# ulchich-variant.net
KiCad netlist of a schematic drawn in Altium Designer
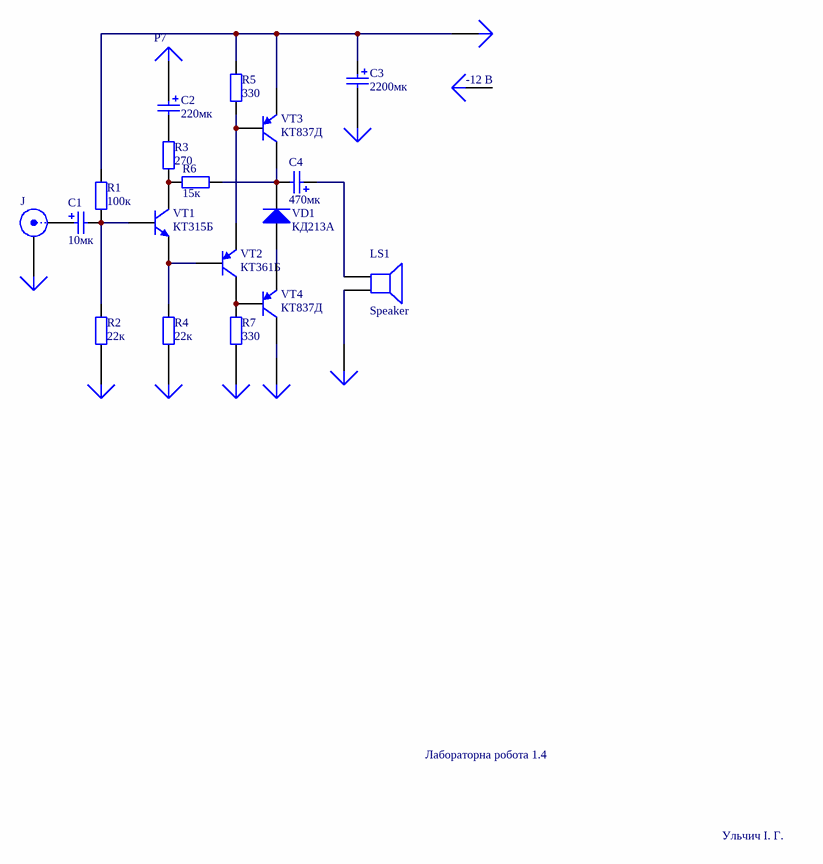
[diagram p0: ulchich-variant.SchDoc]

(export (version "E")
  (design (tool "Eeschema 10.0.6"))
  (components
    (comp (ref "C1")
      (value "10мк")
      (footprint "CAPPA14.05-10.5x6.3")
      (description "Polarized Capacitor (Axial)")
      (fields (field (name "Comment") "Cap Pol2") (field (name "PUBLISHER") "Altium Limited"))
      (libsource (lib "Miscellaneous Devices") (part "Cap Pol2"))
    )
    (comp (ref "C2")
      (value "220мк")
      (footprint "CAPPA14.05-10.5x6.3")
      (description "Polarized Capacitor (Axial)")
      (fields (field (name "Comment") "Cap Pol2") (field (name "PUBLISHER") "Altium Limited"))
      (libsource (lib "Miscellaneous Devices") (part "Cap Pol2"))
    )
    (comp (ref "C3")
      (value "2200мк")
      (footprint "CAPPA14.05-10.5x6.3")
      (description "Polarized Capacitor (Axial)")
      (fields (field (name "Comment") "Cap Pol2") (field (name "PUBLISHER") "Altium Limited"))
      (libsource (lib "Miscellaneous Devices") (part "Cap Pol2"))
    )
    (comp (ref "C4")
      (value "470мк")
      (footprint "CAPPA14.05-10.5x6.3")
      (description "Polarized Capacitor (Axial)")
      (fields (field (name "Comment") "Cap Pol2") (field (name "PUBLISHER") "Altium Limited"))
      (libsource (lib "Miscellaneous Devices") (part "Cap Pol2"))
    )
    (comp (ref "J")
      (value "BNC")
      (footprint "BNC_RA CON")
      (description "BNC Elbow Connector")
      (fields (field (name "PUBLISHER") "Altium Limited"))
      (libsource (lib "Miscellaneous Connectors") (part "BNC"))
    )
    (comp (ref "LS1")
      (value "Speaker")
      (footprint "PIN2")
      (description "Loudspeaker")
      (fields (field (name "PUBLISHER") "Altium Limited"))
      (libsource (lib "Miscellaneous Devices") (part "Speaker"))
    )
    (comp (ref "P1")
      (value "Plug")
      (footprint "PIN1")
      (fields (field (name "PUBLISHER") "Altium Limited"))
      (libsource (lib "Miscellaneous Connectors") (part "Plug"))
    )
    (comp (ref "P2")
      (value "Plug")
      (footprint "PIN1")
      (fields (field (name "PUBLISHER") "Altium Limited"))
      (libsource (lib "Miscellaneous Connectors") (part "Plug"))
    )
    (comp (ref "P3")
      (value "Plug")
      (footprint "PIN1")
      (fields (field (name "PUBLISHER") "Altium Limited"))
      (libsource (lib "Miscellaneous Connectors") (part "Plug"))
    )
    (comp (ref "P4")
      (value "Plug")
      (footprint "PIN1")
      (fields (field (name "PUBLISHER") "Altium Limited"))
      (libsource (lib "Miscellaneous Connectors") (part "Plug"))
    )
    (comp (ref "P5")
      (value "Plug")
      (footprint "PIN1")
      (fields (field (name "PUBLISHER") "Altium Limited"))
      (libsource (lib "Miscellaneous Connectors") (part "Plug"))
    )
    (comp (ref "P6")
      (value "Plug")
      (footprint "PIN1")
      (fields (field (name "PUBLISHER") "Altium Limited"))
      (libsource (lib "Miscellaneous Connectors") (part "Plug"))
    )
    (comp (ref "P7")
      (value "Plug")
      (footprint "PIN1")
      (fields (field (name "PUBLISHER") "Altium Limited"))
      (libsource (lib "Miscellaneous Connectors") (part "Plug"))
    )
    (comp (ref "P8")
      (value "Plug")
      (footprint "PIN1")
      (fields (field (name "PUBLISHER") "Altium Limited"))
      (libsource (lib "Miscellaneous Connectors") (part "Plug"))
    )
    (comp (ref "P9")
      (value "Plug")
      (footprint "PIN1")
      (fields (field (name "PUBLISHER") "Altium Limited"))
      (libsource (lib "Miscellaneous Connectors") (part "Plug"))
    )
    (comp (ref "P10")
      (value "-12 В")
      (footprint "PIN1")
      (description "Plug")
      (fields (field (name "PUBLISHER") "Altium Limited"))
      (libsource (lib "Miscellaneous Connectors") (part "Plug"))
    )
    (comp (ref "R1")
      (value "100к")
      (footprint "AXIAL-0.4")
      (description "Resistor")
      (fields (field (name "Comment") "Res2") (field (name "PUBLISHER") "Altium Limited"))
      (libsource (lib "Miscellaneous Devices") (part "Res2"))
    )
    (comp (ref "R2")
      (value "22к")
      (footprint "AXIAL-0.4")
      (description "Resistor")
      (fields (field (name "Comment") "Res2") (field (name "PUBLISHER") "Altium Limited"))
      (libsource (lib "Miscellaneous Devices") (part "Res2"))
    )
    (comp (ref "R3")
      (value "270")
      (footprint "AXIAL-0.4")
      (description "Resistor")
      (fields (field (name "Comment") "Res2") (field (name "PUBLISHER") "Altium Limited"))
      (libsource (lib "Miscellaneous Devices") (part "Res2"))
    )
    (comp (ref "R4")
      (value "22к")
      (footprint "AXIAL-0.4")
      (description "Resistor")
      (fields (field (name "Comment") "Res2") (field (name "PUBLISHER") "Altium Limited"))
      (libsource (lib "Miscellaneous Devices") (part "Res2"))
    )
    (comp (ref "R5")
      (value "330")
      (footprint "AXIAL-0.4")
      (description "Resistor")
      (fields (field (name "Comment") "Res2") (field (name "PUBLISHER") "Altium Limited"))
      (libsource (lib "Miscellaneous Devices") (part "Res2"))
    )
    (comp (ref "R6")
      (value "15к")
      (footprint "AXIAL-0.4")
      (description "Resistor")
      (fields (field (name "Comment") "Res2") (field (name "PUBLISHER") "Altium Limited"))
      (libsource (lib "") (part "Res2_1"))
    )
    (comp (ref "R7")
      (value "330")
      (footprint "AXIAL-0.4")
      (description "Resistor")
      (fields (field (name "Comment") "Res2") (field (name "PUBLISHER") "Altium Limited"))
      (libsource (lib "Miscellaneous Devices") (part "Res2"))
    )
    (comp (ref "VD1")
      (value "КД213А")
      (footprint "SMC")
      (description "Default Diode")
      (fields (field (name "PUBLISHER") "Altium Limited"))
      (libsource (lib "Miscellaneous Devices") (part "Diode"))
    )
    (comp (ref "VT1")
      (value "КТ315Б")
      (footprint "TO-226")
      (description "NPN Bipolar Transistor")
      (fields (field (name "PUBLISHER") "Altium Limited"))
      (libsource (lib "Miscellaneous Devices") (part "NPN"))
    )
    (comp (ref "VT2")
      (value "КТ361Б")
      (footprint "SOT-23B")
      (description "PNP Bipolar Transistor")
      (fields (field (name "PUBLISHER") "Altium Limited"))
      (libsource (lib "Miscellaneous Devices") (part "PNP"))
    )
    (comp (ref "VT3")
      (value "КТ837Д")
      (footprint "SOT-23B")
      (description "PNP Bipolar Transistor")
      (fields (field (name "PUBLISHER") "Altium Limited"))
      (libsource (lib "Miscellaneous Devices") (part "PNP"))
    )
    (comp (ref "VT4")
      (value "КТ837Д")
      (footprint "SOT-23B")
      (description "PNP Bipolar Transistor")
      (fields (field (name "PUBLISHER") "Altium Limited"))
      (libsource (lib "Miscellaneous Devices") (part "PNP"))
    )
  )
  (nets
    (net (code "1") (name "Net-(C2-Pad1)") (class "Default")
      (node (ref "C2") (pin "1") (pinfunction "1_1") (pintype "passive"))
      (node (ref "P7") (pin "1") (pinfunction "1_1") (pintype "passive"))
    )
    (net (code "2") (name "Net-(C2-Pad2)") (class "Default")
      (node (ref "C2") (pin "2") (pinfunction "2_2") (pintype "passive"))
      (node (ref "R3") (pin "2") (pinfunction "2_2") (pintype "passive"))
    )
    (net (code "3") (name "Net-(C3-Pad2)") (class "Default")
      (node (ref "C3") (pin "2") (pinfunction "2_2") (pintype "passive"))
      (node (ref "P1") (pin "1") (pinfunction "1_1") (pintype "passive"))
    )
    (net (code "4") (name "Net-(C4-Pad1)") (class "Default")
      (node (ref "C4") (pin "1") (pinfunction "1_1") (pintype "passive"))
      (node (ref "LS1") (pin "1") (pinfunction "1_1") (pintype "passive"))
    )
    (net (code "5") (name "Net-(J-X)") (class "Default")
      (node (ref "C1") (pin "1") (pinfunction "1_1") (pintype "passive"))
      (node (ref "J") (pin "1") (pinfunction "X_1") (pintype "passive"))
    )
    (net (code "6") (name "Net-(J-Y)") (class "Default")
      (node (ref "J") (pin "2") (pinfunction "Y_2") (pintype "passive"))
      (node (ref "P9") (pin "1") (pinfunction "1_1") (pintype "passive"))
    )
    (net (code "7") (name "Net-(LS1-Pad2)") (class "Default")
      (node (ref "LS1") (pin "2") (pinfunction "2_2") (pintype "passive"))
      (node (ref "P2") (pin "1") (pinfunction "1_1") (pintype "passive"))
    )
    (net (code "8") (name "Net-(P3-Pad1)") (class "Default")
      (node (ref "P3") (pin "1") (pinfunction "1_1") (pintype "passive"))
      (node (ref "R7") (pin "1") (pinfunction "1_1") (pintype "passive"))
    )
    (net (code "9") (name "Net-(P4-Pad1)") (class "Default")
      (node (ref "P4") (pin "1") (pinfunction "1_1") (pintype "passive"))
      (node (ref "R4") (pin "1") (pinfunction "1_1") (pintype "passive"))
    )
    (net (code "10") (name "Net-(P5-Pad1)") (class "Default")
      (node (ref "P5") (pin "1") (pinfunction "1_1") (pintype "passive"))
      (node (ref "R2") (pin "1") (pinfunction "1_1") (pintype "passive"))
    )
    (net (code "11") (name "Net-(VD1-A)") (class "Default")
      (node (ref "VD1") (pin "1") (pinfunction "A_1") (pintype "passive"))
      (node (ref "VT4") (pin "3") (pinfunction "E_3") (pintype "passive"))
    )
    (net (code "12") (name "Net-(VD1-K)") (class "Default")
      (node (ref "C4") (pin "2") (pinfunction "2_2") (pintype "passive"))
      (node (ref "R6") (pin "2") (pinfunction "2_2") (pintype "passive"))
      (node (ref "VD1") (pin "2") (pinfunction "K_2") (pintype "passive"))
      (node (ref "VT3") (pin "1") (pinfunction "C_1") (pintype "passive"))
    )
    (net (code "13") (name "Net-(VT1-B)") (class "Default")
      (node (ref "C1") (pin "2") (pinfunction "2_2") (pintype "passive"))
      (node (ref "R1") (pin "1") (pinfunction "1_1") (pintype "passive"))
      (node (ref "R2") (pin "2") (pinfunction "2_2") (pintype "passive"))
      (node (ref "VT1") (pin "2") (pinfunction "B_2") (pintype "passive"))
    )
    (net (code "14") (name "Net-(VT1-C)") (class "Default")
      (node (ref "R3") (pin "1") (pinfunction "1_1") (pintype "passive"))
      (node (ref "R6") (pin "1") (pinfunction "1_1") (pintype "passive"))
      (node (ref "VT1") (pin "1") (pinfunction "C_1") (pintype "passive"))
    )
    (net (code "15") (name "Net-(VT1-E)") (class "Default")
      (node (ref "R4") (pin "2") (pinfunction "2_2") (pintype "passive"))
      (node (ref "VT1") (pin "3") (pinfunction "E_3") (pintype "passive"))
      (node (ref "VT2") (pin "2") (pinfunction "B_2") (pintype "passive"))
    )
    (net (code "16") (name "Net-(VT2-C)") (class "Default")
      (node (ref "R7") (pin "2") (pinfunction "2_2") (pintype "passive"))
      (node (ref "VT2") (pin "1") (pinfunction "C_1") (pintype "passive"))
      (node (ref "VT4") (pin "2") (pinfunction "B_2") (pintype "passive"))
    )
    (net (code "17") (name "Net-(VT2-E)") (class "Default")
      (node (ref "R5") (pin "1") (pinfunction "1_1") (pintype "passive"))
      (node (ref "VT2") (pin "3") (pinfunction "E_3") (pintype "passive"))
      (node (ref "VT3") (pin "2") (pinfunction "B_2") (pintype "passive"))
    )
    (net (code "18") (name "Net-(VT3-E)") (class "Default")
      (node (ref "C3") (pin "1") (pinfunction "1_1") (pintype "passive"))
      (node (ref "P6") (pin "1") (pinfunction "1_1") (pintype "passive"))
      (node (ref "R1") (pin "2") (pinfunction "2_2") (pintype "passive"))
      (node (ref "R5") (pin "2") (pinfunction "2_2") (pintype "passive"))
      (node (ref "VT3") (pin "3") (pinfunction "E_3") (pintype "passive"))
    )
    (net (code "19") (name "Net-(VT4-C)") (class "Default")
      (node (ref "P8") (pin "1") (pinfunction "1_1") (pintype "passive"))
      (node (ref "VT4") (pin "1") (pinfunction "C_1") (pintype "passive"))
    )
    (net (code "20") (name "unconnected-(P10-Pad1)") (class "Default")
      (node (ref "P10") (pin "1") (pinfunction "1_1") (pintype "passive"))
    )
  )
)
